# blink1mk3_micro1b.net
KiCad netlist of a schematic drawn in EAGLE
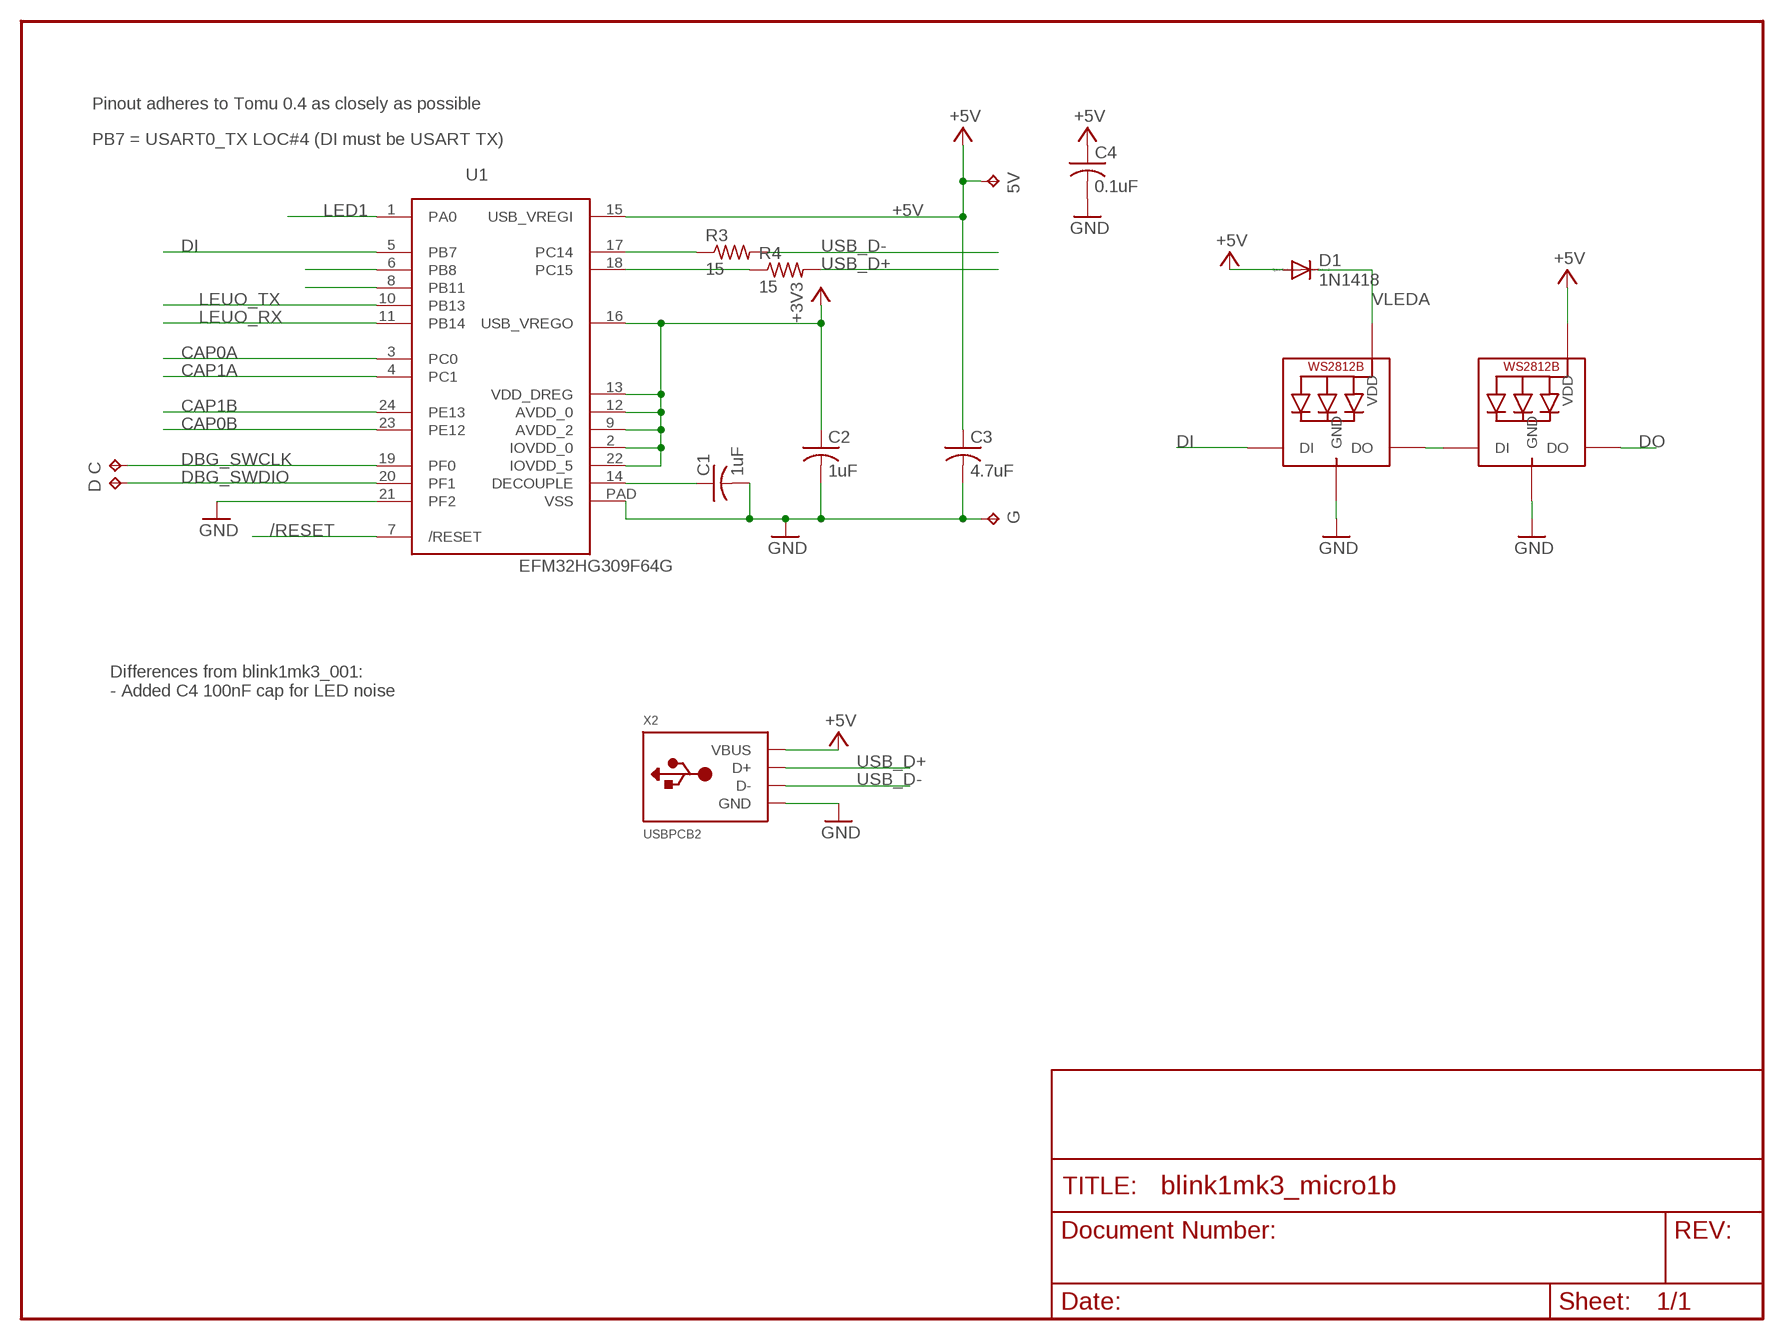
[diagram p0: schematic, sheet 1]

(export (version "E")
  (design (tool "Eeschema 10.0.6"))
  (components
    (comp (ref "5V")
      (value "TPTP10R")
      (footprint "eagle-import:TP10R")
      (libsource (lib "eagle-import") (part "TPTP10R"))
    )
    (comp (ref "C")
      (value "TPTP10R")
      (footprint "eagle-import:TP10R")
      (libsource (lib "eagle-import") (part "TPTP10R"))
    )
    (comp (ref "C1")
      (value "1uF")
      (footprint "eagle-import:C0402")
      (libsource (lib "eagle-import") (part "C-USC0402"))
    )
    (comp (ref "C2")
      (value "1uF")
      (footprint "eagle-import:C0402")
      (libsource (lib "eagle-import") (part "C-USC0402"))
    )
    (comp (ref "C3")
      (value "4.7uF")
      (footprint "eagle-import:C0402")
      (libsource (lib "eagle-import") (part "C-USC0402"))
    )
    (comp (ref "C4")
      (value "0.1uF")
      (footprint "eagle-import:C0402")
      (libsource (lib "eagle-import") (part "C-USC0402"))
    )
    (comp (ref "D")
      (value "TPTP10R")
      (footprint "eagle-import:TP10R")
      (libsource (lib "eagle-import") (part "TPTP10R"))
    )
    (comp (ref "D1")
      (value "1N1418")
      (footprint "eagle-import:SOD523")
      (libsource (lib "eagle-import") (part "DIODE-SOD523"))
    )
    (comp (ref "G")
      (value "TPTP10SQ")
      (footprint "eagle-import:TP10SQ")
      (libsource (lib "eagle-import") (part "TPTP10SQ"))
    )
    (comp (ref "LED1")
      (value "WS2812B4020SIDE")
      (footprint "eagle-import:SK6812-SIDE")
      (libsource (lib "eagle-import") (part "WS2812B4020SIDE"))
    )
    (comp (ref "LED2")
      (value "WS2812B4020SIDE")
      (footprint "eagle-import:SK6812-SIDE")
      (libsource (lib "eagle-import") (part "WS2812B4020SIDE"))
    )
    (comp (ref "R3")
      (value "15")
      (footprint "eagle-import:R0402")
      (libsource (lib "eagle-import") (part "R-US_R0402"))
    )
    (comp (ref "R4")
      (value "15")
      (footprint "eagle-import:R0402")
      (libsource (lib "eagle-import") (part "R-US_R0402"))
    )
    (comp (ref "U1")
      (value "EFM32HG309F64G")
      (footprint "eagle-import:QFN24PAD")
      (libsource (lib "eagle-import") (part "EFM32HG309F64G"))
    )
    (comp (ref "X2")
      (value "USBPCB2")
      (footprint "eagle-import:USB-A-PCB-2")
      (libsource (lib "eagle-import") (part "USBPCB2"))
    )
  )
  (nets
    (net (code "1") (name "+3V3") (class "Default")
      (node (ref "C2") (pin "1") (pinfunction "1_1") (pintype "passive"))
      (node (ref "U1") (pin "12") (pinfunction "AVDD_0_12") (pintype "bidirectional"))
      (node (ref "U1") (pin "13") (pinfunction "VDD_DREG_13") (pintype "bidirectional"))
      (node (ref "U1") (pin "16") (pinfunction "USB_VREGO_16") (pintype "bidirectional"))
      (node (ref "U1") (pin "2") (pinfunction "IOVDD_0_2") (pintype "bidirectional"))
      (node (ref "U1") (pin "22") (pinfunction "IOVDD_5_22") (pintype "bidirectional"))
      (node (ref "U1") (pin "9") (pinfunction "AVDD_2_9") (pintype "bidirectional"))
    )
    (net (code "2") (name "+5V") (class "Default")
      (node (ref "5V") (pin "TP") (pinfunction "TP_TP") (pintype "input"))
      (node (ref "C3") (pin "1") (pinfunction "1_1") (pintype "passive"))
      (node (ref "C4") (pin "1") (pinfunction "1_1") (pintype "passive"))
      (node (ref "D1") (pin "A") (pinfunction "A_A") (pintype "passive"))
      (node (ref "LED2") (pin "1-VDD") (pinfunction "VDD_1-VDD") (pintype "power_in"))
      (node (ref "U1") (pin "15") (pinfunction "USB_VREGI_15") (pintype "bidirectional"))
      (node (ref "X2") (pin "5V") (pinfunction "VBUS_5V") (pintype "power_in"))
    )
    (net (code "3") (name "/CAP0A") (class "Default")
      (node (ref "U1") (pin "3") (pinfunction "PC0_3") (pintype "bidirectional"))
    )
    (net (code "4") (name "/CAP0B") (class "Default")
      (node (ref "U1") (pin "23") (pinfunction "PE12_23") (pintype "bidirectional"))
    )
    (net (code "5") (name "/CAP1A") (class "Default")
      (node (ref "U1") (pin "4") (pinfunction "PC1_4") (pintype "bidirectional"))
    )
    (net (code "6") (name "/CAP1B") (class "Default")
      (node (ref "U1") (pin "24") (pinfunction "PE13_24") (pintype "bidirectional"))
    )
    (net (code "7") (name "/DBG_SWCLK") (class "Default")
      (node (ref "C") (pin "TP") (pinfunction "TP_TP") (pintype "input"))
      (node (ref "U1") (pin "19") (pinfunction "PF0_19") (pintype "bidirectional"))
    )
    (net (code "8") (name "/DBG_SWDIO") (class "Default")
      (node (ref "D") (pin "TP") (pinfunction "TP_TP") (pintype "input"))
      (node (ref "U1") (pin "20") (pinfunction "PF1_20") (pintype "bidirectional"))
    )
    (net (code "9") (name "/DI") (class "Default")
      (node (ref "LED1") (pin "4-DIN") (pinfunction "DI_4-DIN") (pintype "input"))
      (node (ref "U1") (pin "5") (pinfunction "PB7_5") (pintype "bidirectional"))
    )
    (net (code "10") (name "/DO") (class "Default")
      (node (ref "LED2") (pin "2-DOUT") (pinfunction "DO_2-DOUT") (pintype "output"))
    )
    (net (code "11") (name "/LED1") (class "Default")
      (node (ref "U1") (pin "1") (pinfunction "PA0_1") (pintype "bidirectional"))
    )
    (net (code "12") (name "/LEUO_RX") (class "Default")
      (node (ref "U1") (pin "11") (pinfunction "PB14_11") (pintype "bidirectional"))
    )
    (net (code "13") (name "/LEUO_TX") (class "Default")
      (node (ref "U1") (pin "10") (pinfunction "PB13_10") (pintype "bidirectional"))
    )
    (net (code "14") (name "/USB_D+") (class "Default")
      (node (ref "R4") (pin "2") (pinfunction "2_2") (pintype "passive"))
      (node (ref "X2") (pin "USB_P") (pinfunction "D+_USB_P") (pintype "bidirectional"))
    )
    (net (code "15") (name "/USB_D-") (class "Default")
      (node (ref "R3") (pin "2") (pinfunction "2_2") (pintype "passive"))
      (node (ref "X2") (pin "USB_M") (pinfunction "D-_USB_M") (pintype "bidirectional"))
    )
    (net (code "16") (name "/VLEDA") (class "Default")
      (node (ref "D1") (pin "C") (pinfunction "C_C") (pintype "passive"))
      (node (ref "LED1") (pin "1-VDD") (pinfunction "VDD_1-VDD") (pintype "power_in"))
    )
    (net (code "17") (name "/{slash}RESET") (class "Default")
      (node (ref "U1") (pin "7") (pinfunction "/RESET_7") (pintype "bidirectional"))
    )
    (net (code "18") (name "GND") (class "Default")
      (node (ref "C1") (pin "2") (pinfunction "2_2") (pintype "passive"))
      (node (ref "C2") (pin "2") (pinfunction "2_2") (pintype "passive"))
      (node (ref "C3") (pin "2") (pinfunction "2_2") (pintype "passive"))
      (node (ref "C4") (pin "2") (pinfunction "2_2") (pintype "passive"))
      (node (ref "G") (pin "TP") (pinfunction "TP_TP") (pintype "input"))
      (node (ref "LED1") (pin "3-GND") (pinfunction "GND_3-GND") (pintype "power_in"))
      (node (ref "LED2") (pin "3-GND") (pinfunction "GND_3-GND") (pintype "power_in"))
      (node (ref "U1") (pin "21") (pinfunction "PF2_21") (pintype "bidirectional"))
      (node (ref "U1") (pin "PAD") (pinfunction "VSS_PAD") (pintype "bidirectional"))
      (node (ref "X2") (pin "GND") (pinfunction "GND_GND") (pintype "power_in"))
    )
    (net (code "19") (name "Net-(LED1-DO)") (class "Default")
      (node (ref "LED1") (pin "2-DOUT") (pinfunction "DO_2-DOUT") (pintype "output"))
      (node (ref "LED2") (pin "4-DIN") (pinfunction "DI_4-DIN") (pintype "input"))
    )
    (net (code "20") (name "Net-(U1-DECOUPLE)") (class "Default")
      (node (ref "C1") (pin "1") (pinfunction "1_1") (pintype "passive"))
      (node (ref "U1") (pin "14") (pinfunction "DECOUPLE_14") (pintype "bidirectional"))
    )
    (net (code "21") (name "Net-(U1-PC14)") (class "Default")
      (node (ref "R3") (pin "1") (pinfunction "1_1") (pintype "passive"))
      (node (ref "U1") (pin "17") (pinfunction "PC14_17") (pintype "bidirectional"))
    )
    (net (code "22") (name "Net-(U1-PC15)") (class "Default")
      (node (ref "R4") (pin "1") (pinfunction "1_1") (pintype "passive"))
      (node (ref "U1") (pin "18") (pinfunction "PC15_18") (pintype "bidirectional"))
    )
    (net (code "23") (name "unconnected-(U1-PB8-Pad6)") (class "Default")
      (node (ref "U1") (pin "6") (pinfunction "PB8_6") (pintype "bidirectional"))
    )
    (net (code "24") (name "unconnected-(U1-PB11-Pad8)") (class "Default")
      (node (ref "U1") (pin "8") (pinfunction "PB11_8") (pintype "bidirectional"))
    )
  )
)
